# Driver.net
KiCad netlist of a schematic drawn in Altium Designer
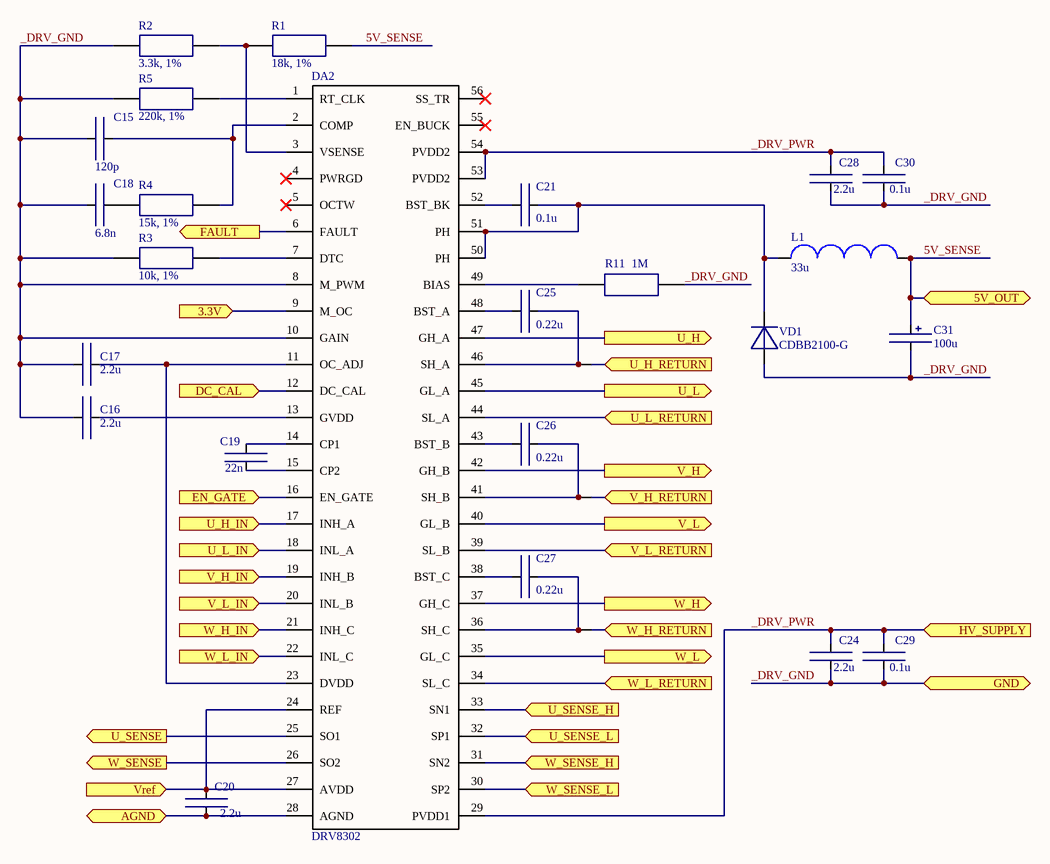
[diagram p0: Driver.SchDoc]

(export (version "E")
  (design (tool "Eeschema 10.0.6"))
  (components
    (comp (ref "C15")
      (value "120p")
      (footprint "Condensator:CAPC1608X08N(0603)")
      (libsource (lib "Condensator") (part "Ceramic Chip Capacitor"))
    )
    (comp (ref "C16")
      (value "2.2u")
      (footprint "Condensator:CAPC1608X08N(0603)")
      (libsource (lib "Condensator") (part "Ceramic Chip Capacitor"))
    )
    (comp (ref "C17")
      (value "2.2u")
      (footprint "Condensator:CAPC1608X08N(0603)")
      (libsource (lib "Condensator") (part "Ceramic Chip Capacitor"))
    )
    (comp (ref "C18")
      (value "6.8n")
      (footprint "Condensator:CAPC1608X08N(0603)")
      (libsource (lib "Condensator") (part "Ceramic Chip Capacitor"))
    )
    (comp (ref "C19")
      (value "22n")
      (footprint "Condensator:CAPC1608X08N(0603)")
      (libsource (lib "Condensator") (part "Ceramic Chip Capacitor"))
    )
    (comp (ref "C20")
      (value "2.2u")
      (footprint "Condensator:CAPC1608X08N(0603)")
      (libsource (lib "Condensator") (part "Ceramic Chip Capacitor"))
    )
    (comp (ref "C21")
      (value "0.1u")
      (footprint "Condensator:CAPC1608X08N(0603)")
      (libsource (lib "Condensator") (part "Ceramic Chip Capacitor"))
    )
    (comp (ref "C24")
      (value "2.2u")
      (footprint "EIA CC1210")
      (libsource (lib "Condensator") (part "Ceramic Chip Capacitor"))
    )
    (comp (ref "C25")
      (value "0.22u")
      (footprint "Condensator:CAPC1608X08N(0603)")
      (libsource (lib "Condensator") (part "Ceramic Chip Capacitor"))
    )
    (comp (ref "C26")
      (value "0.22u")
      (footprint "Condensator:CAPC1608X08N(0603)")
      (libsource (lib "Condensator") (part "Ceramic Chip Capacitor"))
    )
    (comp (ref "C27")
      (value "0.22u")
      (footprint "Condensator:CAPC1608X08N(0603)")
      (libsource (lib "Condensator") (part "Ceramic Chip Capacitor"))
    )
    (comp (ref "C28")
      (value "2.2u")
      (footprint "EIA CC1210")
      (libsource (lib "Condensator") (part "Ceramic Chip Capacitor"))
    )
    (comp (ref "C29")
      (value "0.1u")
      (footprint "Condensator:C0805")
      (libsource (lib "Condensator") (part "Ceramic Chip Capacitor"))
    )
    (comp (ref "C30")
      (value "0.1u")
      (footprint "Condensator:C0805")
      (libsource (lib "Condensator") (part "Ceramic Chip Capacitor"))
    )
    (comp (ref "C31")
      (value "100u")
      (footprint "CAP type B")
      (libsource (lib "Condensator") (part "Tantalum Chip Capacitor"))
    )
    (comp (ref "DA2")
      (value "DRV8302")
      (footprint "Mikrosxema:HTSSOP56(L)")
      (libsource (lib "Mikrosxema") (part "DRV8302"))
    )
    (comp (ref "L1") (value "33u") (footprint "DR74") (libsource (lib "Drossel") (part "DR74")))
    (comp (ref "NT1")
      (value "NET_TIE")
      (footprint "NET_TIE")
      (description "Net tie")
      (libsource (lib "CustomLib") (part "Net tie"))
    )
    (comp (ref "NT2")
      (value "NET_TIE")
      (footprint "NET_TIE")
      (description "Net tie")
      (libsource (lib "CustomLib") (part "Net tie"))
    )
    (comp (ref "NT3")
      (value "NET_TIE")
      (footprint "NET_TIE")
      (description "Net tie")
      (libsource (lib "CustomLib") (part "Net tie"))
    )
    (comp (ref "R1")
      (value "18k, 1%")
      (footprint "Rezistor:RESC1608X05N(0603)")
      (libsource (lib "Rezistor") (part "SMD"))
    )
    (comp (ref "R2")
      (value "3.3k, 1%")
      (footprint "Rezistor:RESC1608X05N(0603)")
      (libsource (lib "Rezistor") (part "SMD"))
    )
    (comp (ref "R3")
      (value "10k, 1%")
      (footprint "Rezistor:RESC1608X05N(0603)")
      (libsource (lib "Rezistor") (part "SMD"))
    )
    (comp (ref "R4")
      (value "15k, 1%")
      (footprint "Rezistor:RESC1608X05N(0603)")
      (libsource (lib "Rezistor") (part "SMD"))
    )
    (comp (ref "R5")
      (value "220k, 1%")
      (footprint "Rezistor:RESC1608X05N(0603)")
      (libsource (lib "Rezistor") (part "SMD"))
    )
    (comp (ref "R11")
      (value "1M")
      (footprint "Rezistor:RESC1608X05N(0603)")
      (libsource (lib "Rezistor") (part "SMD"))
    )
    (comp (ref "VD1")
      (value "CDBB2100-G")
      (footprint "SMA(DO-214AC)")
      (libsource (lib "diod") (part "ES1A...D"))
    )
  )
  (nets
    (net (code "1") (name "/3.3V") (class "Default")
      (node (ref "DA2") (pin "9") (pinfunction "M_OC_9") (pintype "passive"))
    )
    (net (code "2") (name "/5V_SENSE") (class "Default")
      (node (ref "C31") (pin "1") (pintype "passive"))
      (node (ref "L1") (pin "2") (pinfunction "2_2") (pintype "passive"))
      (node (ref "R1") (pin "1") (pintype "passive"))
    )
    (net (code "3") (name "/AGND") (class "Default")
      (node (ref "C20") (pin "2") (pintype "passive"))
      (node (ref "DA2") (pin "28") (pinfunction "AGND_28") (pintype "passive"))
    )
    (net (code "4") (name "/DC_CAL") (class "Default")
      (node (ref "DA2") (pin "12") (pinfunction "DC_CAL_12") (pintype "passive"))
    )
    (net (code "5") (name "/EN_GATE") (class "Default")
      (node (ref "DA2") (pin "16") (pinfunction "EN_GATE_16") (pintype "passive"))
    )
    (net (code "6") (name "/FAULT") (class "Default")
      (node (ref "DA2") (pin "6") (pinfunction "FAULT_6") (pintype "passive"))
    )
    (net (code "7") (name "/U_H") (class "Default")
      (node (ref "DA2") (pin "47") (pinfunction "GH_A_47") (pintype "passive"))
    )
    (net (code "8") (name "/U_H_IN") (class "Default")
      (node (ref "DA2") (pin "17") (pinfunction "INH_A_17") (pintype "passive"))
    )
    (net (code "9") (name "/U_H_RETURN") (class "Default")
      (node (ref "NT1") (pin "1") (pinfunction "1_1") (pintype "passive"))
    )
    (net (code "10") (name "/U_L") (class "Default")
      (node (ref "DA2") (pin "45") (pinfunction "GL_A_45") (pintype "passive"))
    )
    (net (code "11") (name "/U_L_IN") (class "Default")
      (node (ref "DA2") (pin "18") (pinfunction "INL_A_18") (pintype "passive"))
    )
    (net (code "12") (name "/U_L_RETURN") (class "Default")
      (node (ref "DA2") (pin "44") (pinfunction "SL_A_44") (pintype "passive"))
    )
    (net (code "13") (name "/U_SENSE") (class "Default")
      (node (ref "DA2") (pin "25") (pinfunction "SO1_25") (pintype "passive"))
    )
    (net (code "14") (name "/U_SENSE_H") (class "Default")
      (node (ref "DA2") (pin "33") (pinfunction "SN1_33") (pintype "passive"))
    )
    (net (code "15") (name "/U_SENSE_L") (class "Default")
      (node (ref "DA2") (pin "32") (pinfunction "SP1_32") (pintype "passive"))
    )
    (net (code "16") (name "/V_H") (class "Default")
      (node (ref "DA2") (pin "42") (pinfunction "GH_B_42") (pintype "passive"))
    )
    (net (code "17") (name "/V_H_IN") (class "Default")
      (node (ref "DA2") (pin "19") (pinfunction "INH_B_19") (pintype "passive"))
    )
    (net (code "18") (name "/V_H_RETURN") (class "Default")
      (node (ref "NT2") (pin "1") (pinfunction "1_1") (pintype "passive"))
    )
    (net (code "19") (name "/V_L") (class "Default")
      (node (ref "DA2") (pin "40") (pinfunction "GL_B_40") (pintype "passive"))
    )
    (net (code "20") (name "/V_L_IN") (class "Default")
      (node (ref "DA2") (pin "20") (pinfunction "INL_B_20") (pintype "passive"))
    )
    (net (code "21") (name "/V_L_RETURN") (class "Default")
      (node (ref "DA2") (pin "39") (pinfunction "SL_B_39") (pintype "passive"))
    )
    (net (code "22") (name "/Vref") (class "Default")
      (node (ref "C20") (pin "1") (pintype "passive"))
      (node (ref "DA2") (pin "24") (pinfunction "REF_24") (pintype "passive"))
      (node (ref "DA2") (pin "27") (pinfunction "AVDD_27") (pintype "passive"))
    )
    (net (code "23") (name "/W_H") (class "Default")
      (node (ref "DA2") (pin "37") (pinfunction "GH_C_37") (pintype "passive"))
    )
    (net (code "24") (name "/W_H_IN") (class "Default")
      (node (ref "DA2") (pin "21") (pinfunction "INH_C_21") (pintype "passive"))
    )
    (net (code "25") (name "/W_H_RETURN") (class "Default")
      (node (ref "NT3") (pin "1") (pinfunction "1_1") (pintype "passive"))
    )
    (net (code "26") (name "/W_L") (class "Default")
      (node (ref "DA2") (pin "35") (pinfunction "GL_C_35") (pintype "passive"))
    )
    (net (code "27") (name "/W_L_IN") (class "Default")
      (node (ref "DA2") (pin "22") (pinfunction "INL_C_22") (pintype "passive"))
    )
    (net (code "28") (name "/W_L_RETURN") (class "Default")
      (node (ref "DA2") (pin "34") (pinfunction "SL_C_34") (pintype "passive"))
    )
    (net (code "29") (name "/W_SENSE") (class "Default")
      (node (ref "DA2") (pin "26") (pinfunction "SO2_26") (pintype "passive"))
    )
    (net (code "30") (name "/W_SENSE_H") (class "Default")
      (node (ref "DA2") (pin "31") (pinfunction "SN2_31") (pintype "passive"))
    )
    (net (code "31") (name "/W_SENSE_L") (class "Default")
      (node (ref "DA2") (pin "30") (pinfunction "SP2_30") (pintype "passive"))
    )
    (net (code "32") (name "/_DRV_GND") (class "Default")
      (node (ref "C15") (pin "1") (pintype "passive"))
      (node (ref "C16") (pin "1") (pintype "passive"))
      (node (ref "C17") (pin "2") (pintype "passive"))
      (node (ref "C18") (pin "1") (pintype "passive"))
      (node (ref "C24") (pin "2") (pintype "passive"))
      (node (ref "C28") (pin "2") (pintype "passive"))
      (node (ref "C29") (pin "2") (pintype "passive"))
      (node (ref "C30") (pin "2") (pintype "passive"))
      (node (ref "C31") (pin "2") (pintype "passive"))
      (node (ref "DA2") (pin "10") (pinfunction "GAIN_10") (pintype "passive"))
      (node (ref "DA2") (pin "8") (pinfunction "M_PWM_8") (pintype "passive"))
      (node (ref "R11") (pin "2") (pintype "passive"))
      (node (ref "R2") (pin "2") (pintype "passive"))
      (node (ref "R3") (pin "1") (pintype "passive"))
      (node (ref "R5") (pin "2") (pintype "passive"))
      (node (ref "VD1") (pin "1") (pintype "passive"))
    )
    (net (code "33") (name "/_DRV_PWR") (class "Default")
      (node (ref "C24") (pin "1") (pintype "passive"))
      (node (ref "C28") (pin "1") (pintype "passive"))
      (node (ref "C29") (pin "1") (pintype "passive"))
      (node (ref "C30") (pin "1") (pintype "passive"))
      (node (ref "DA2") (pin "29") (pinfunction "PVDD1_29") (pintype "passive"))
      (node (ref "DA2") (pin "53") (pinfunction "PVDD2_53") (pintype "passive"))
      (node (ref "DA2") (pin "54") (pinfunction "PVDD2_54") (pintype "passive"))
    )
    (net (code "34") (name "Net-(C18-Pad2)") (class "Default")
      (node (ref "C18") (pin "2") (pintype "passive"))
      (node (ref "R4") (pin "1") (pintype "passive"))
    )
    (net (code "35") (name "Net-(C21-Pad2)") (class "Default")
      (node (ref "C21") (pin "2") (pintype "passive"))
      (node (ref "DA2") (pin "50") (pinfunction "PH_50") (pintype "passive"))
      (node (ref "DA2") (pin "51") (pinfunction "PH_51") (pintype "passive"))
      (node (ref "L1") (pin "1") (pinfunction "1_1") (pintype "passive"))
      (node (ref "VD1") (pin "2") (pintype "passive"))
    )
    (net (code "36") (name "Net-(DA2-BIAS)") (class "Default")
      (node (ref "DA2") (pin "49") (pinfunction "BIAS_49") (pintype "passive"))
      (node (ref "R11") (pin "1") (pintype "passive"))
    )
    (net (code "37") (name "Net-(DA2-BST_A)") (class "Default")
      (node (ref "C25") (pin "1") (pintype "passive"))
      (node (ref "DA2") (pin "48") (pinfunction "BST_A_48") (pintype "passive"))
    )
    (net (code "38") (name "Net-(DA2-BST_B)") (class "Default")
      (node (ref "C26") (pin "1") (pintype "passive"))
      (node (ref "DA2") (pin "43") (pinfunction "BST_B_43") (pintype "passive"))
    )
    (net (code "39") (name "Net-(DA2-BST_BK)") (class "Default")
      (node (ref "C21") (pin "1") (pintype "passive"))
      (node (ref "DA2") (pin "52") (pinfunction "BST_BK_52") (pintype "passive"))
    )
    (net (code "40") (name "Net-(DA2-BST_C)") (class "Default")
      (node (ref "C27") (pin "1") (pintype "passive"))
      (node (ref "DA2") (pin "38") (pinfunction "BST_C_38") (pintype "passive"))
    )
    (net (code "41") (name "Net-(DA2-COMP)") (class "Default")
      (node (ref "C15") (pin "2") (pintype "passive"))
      (node (ref "DA2") (pin "2") (pinfunction "COMP_2") (pintype "passive"))
      (node (ref "R4") (pin "2") (pintype "passive"))
    )
    (net (code "42") (name "Net-(DA2-CP1)") (class "Default")
      (node (ref "C19") (pin "1") (pintype "passive"))
      (node (ref "DA2") (pin "14") (pinfunction "CP1_14") (pintype "passive"))
    )
    (net (code "43") (name "Net-(DA2-CP2)") (class "Default")
      (node (ref "C19") (pin "2") (pintype "passive"))
      (node (ref "DA2") (pin "15") (pinfunction "CP2_15") (pintype "passive"))
    )
    (net (code "44") (name "Net-(DA2-DTC)") (class "Default")
      (node (ref "DA2") (pin "7") (pinfunction "DTC_7") (pintype "passive"))
      (node (ref "R3") (pin "2") (pintype "passive"))
    )
    (net (code "45") (name "Net-(DA2-DVDD)") (class "Default")
      (node (ref "C17") (pin "1") (pintype "passive"))
      (node (ref "DA2") (pin "11") (pinfunction "OC_ADJ_11") (pintype "passive"))
      (node (ref "DA2") (pin "23") (pinfunction "DVDD_23") (pintype "passive"))
    )
    (net (code "46") (name "Net-(DA2-GVDD)") (class "Default")
      (node (ref "C16") (pin "2") (pintype "passive"))
      (node (ref "DA2") (pin "13") (pinfunction "GVDD_13") (pintype "passive"))
    )
    (net (code "47") (name "Net-(DA2-RT_CLK)") (class "Default")
      (node (ref "DA2") (pin "1") (pinfunction "RT_CLK_1") (pintype "passive"))
      (node (ref "R5") (pin "1") (pintype "passive"))
    )
    (net (code "48") (name "Net-(DA2-SH_A)") (class "Default")
      (node (ref "C25") (pin "2") (pintype "passive"))
      (node (ref "DA2") (pin "46") (pinfunction "SH_A_46") (pintype "passive"))
      (node (ref "NT1") (pin "2") (pinfunction "2_2") (pintype "passive"))
    )
    (net (code "49") (name "Net-(DA2-SH_B)") (class "Default")
      (node (ref "C26") (pin "2") (pintype "passive"))
      (node (ref "DA2") (pin "41") (pinfunction "SH_B_41") (pintype "passive"))
      (node (ref "NT2") (pin "2") (pinfunction "2_2") (pintype "passive"))
    )
    (net (code "50") (name "Net-(DA2-SH_C)") (class "Default")
      (node (ref "C27") (pin "2") (pintype "passive"))
      (node (ref "DA2") (pin "36") (pinfunction "SH_C_36") (pintype "passive"))
      (node (ref "NT3") (pin "2") (pinfunction "2_2") (pintype "passive"))
    )
    (net (code "51") (name "Net-(DA2-VSENSE)") (class "Default")
      (node (ref "DA2") (pin "3") (pinfunction "VSENSE_3") (pintype "passive"))
      (node (ref "R1") (pin "2") (pintype "passive"))
      (node (ref "R2") (pin "1") (pintype "passive"))
    )
    (net (code "52") (name "unconnected-(DA2-EN_BUCK-Pad55)") (class "Default")
      (node (ref "DA2") (pin "55") (pinfunction "EN_BUCK_55") (pintype "passive+no_connect"))
    )
    (net (code "53") (name "unconnected-(DA2-OCTW-Pad5)") (class "Default")
      (node (ref "DA2") (pin "5") (pinfunction "OCTW_5") (pintype "passive+no_connect"))
    )
    (net (code "54") (name "unconnected-(DA2-PWRGD-Pad4)") (class "Default")
      (node (ref "DA2") (pin "4") (pinfunction "PWRGD_4") (pintype "passive+no_connect"))
    )
    (net (code "55") (name "unconnected-(DA2-Pad57)") (class "Default")
      (node (ref "DA2") (pin "57") (pintype "passive"))
    )
    (net (code "56") (name "unconnected-(DA2-SS_TR-Pad56)") (class "Default")
      (node (ref "DA2") (pin "56") (pinfunction "SS_TR_56") (pintype "passive+no_connect"))
    )
  )
)
